# tiny.net
KiCad netlist of a schematic drawn in EAGLE
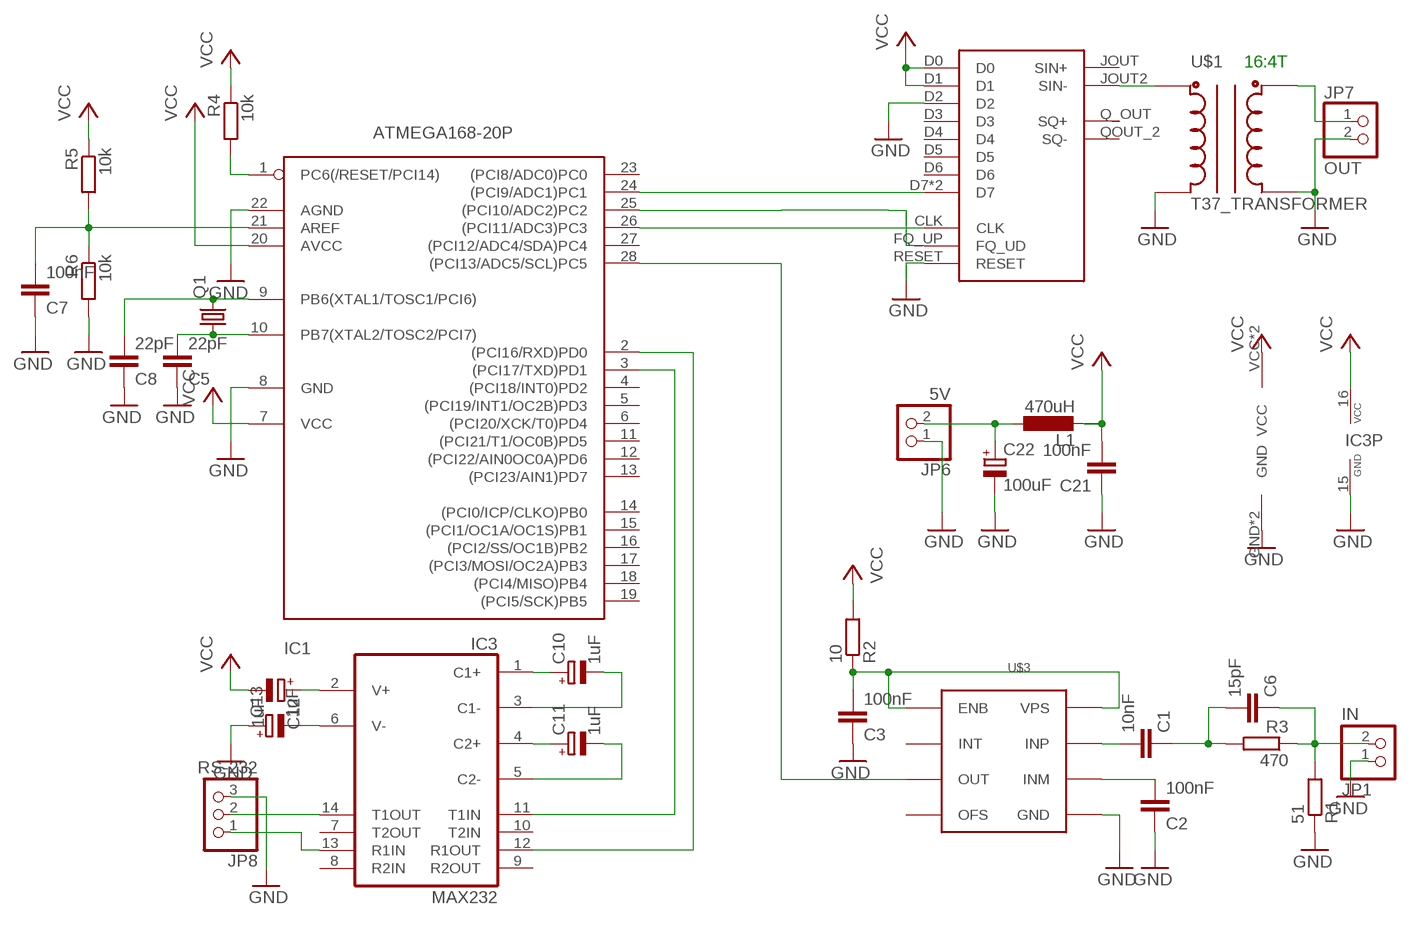
[diagram p0: schematic, sheet 1]

(export (version "E")
  (design (tool "Eeschema 10.0.6"))
  (components
    (comp (ref "C1")
      (value "10nF")
      (footprint "eagle-import:C050-025X075")
      (libsource (lib "eagle-import") (part "C-EU050-025X075"))
    )
    (comp (ref "C2")
      (value "100nF")
      (footprint "eagle-import:C025-025X050")
      (libsource (lib "eagle-import") (part "C-EU025-025X050"))
    )
    (comp (ref "C3")
      (value "100nF")
      (footprint "eagle-import:C025-025X050")
      (libsource (lib "eagle-import") (part "C-EU025-025X050"))
    )
    (comp (ref "C5")
      (value "22pF")
      (footprint "eagle-import:C050-025X075")
      (libsource (lib "eagle-import") (part "C-EU050-025X075"))
    )
    (comp (ref "C6")
      (value "15pF")
      (footprint "eagle-import:C050-025X075")
      (libsource (lib "eagle-import") (part "C-EU050-025X075"))
    )
    (comp (ref "C7")
      (value "100nF")
      (footprint "eagle-import:C025-025X050")
      (libsource (lib "eagle-import") (part "C-EU025-025X050"))
    )
    (comp (ref "C8")
      (value "22pF")
      (footprint "eagle-import:C025-025X050")
      (libsource (lib "eagle-import") (part "C-EU025-025X050"))
    )
    (comp (ref "C10")
      (value "1uF")
      (footprint "eagle-import:E5-5")
      (libsource (lib "eagle-import") (part "CPOL-EUE5-5"))
    )
    (comp (ref "C11")
      (value "1uF")
      (footprint "eagle-import:E2,5-5")
      (libsource (lib "eagle-import") (part "CPOL-EUE2.5-5"))
    )
    (comp (ref "C12")
      (value "1uF")
      (footprint "eagle-import:E2,5-6")
      (libsource (lib "eagle-import") (part "CPOL-EUE2.5-6"))
    )
    (comp (ref "C13")
      (value "1uF")
      (footprint "eagle-import:E5-5")
      (libsource (lib "eagle-import") (part "CPOL-EUE5-5"))
    )
    (comp (ref "C21")
      (value "100nF")
      (footprint "eagle-import:C025-025X050")
      (libsource (lib "eagle-import") (part "C-EU025-025X050"))
    )
    (comp (ref "C22")
      (value "100uF")
      (footprint "eagle-import:E2,5-6")
      (libsource (lib "eagle-import") (part "CPOL-EUE2.5-6"))
    )
    (comp (ref "IC1")
      (value "ATMEGA168-20P")
      (footprint "eagle-import:DIL28-3")
      (libsource (lib "eagle-import") (part "ATMEGA168P-20"))
    )
    (comp (ref "IC3")
      (value "MAX232")
      (footprint "eagle-import:DIL16")
      (fields (field (name "MF") "MAXIM") (field (name "MPN") "MAX232ACPE+"))
      (libsource (lib "eagle-import") (part "MAX232"))
    )
    (comp (ref "JP1")
      (value "IN")
      (footprint "eagle-import:1X02")
      (libsource (lib "eagle-import") (part "PINHD-1X2"))
    )
    (comp (ref "JP6")
      (value "5V")
      (footprint "eagle-import:1X02")
      (libsource (lib "eagle-import") (part "PINHD-1X2"))
    )
    (comp (ref "JP7")
      (value "OUT")
      (footprint "eagle-import:1X02")
      (libsource (lib "eagle-import") (part "PINHD-1X2"))
    )
    (comp (ref "JP8")
      (value "RS-232")
      (footprint "eagle-import:1X03")
      (libsource (lib "eagle-import") (part "PINHD-1X3"))
    )
    (comp (ref "L1")
      (value "470uH")
      (footprint "eagle-import:0204_7")
      (libsource (lib "eagle-import") (part "L-EU0204/7"))
    )
    (comp (ref "Q1")
      (value "CRYSTALHC18U-V")
      (footprint "eagle-import:HC18U-V")
      (libsource (lib "eagle-import") (part "CRYSTALHC18U-V"))
    )
    (comp (ref "R1")
      (value "51")
      (footprint "eagle-import:0204V")
      (libsource (lib "eagle-import") (part "R-EU_0204/2V"))
    )
    (comp (ref "R2")
      (value "10")
      (footprint "eagle-import:0204_7")
      (libsource (lib "eagle-import") (part "R-EU_0204/7"))
    )
    (comp (ref "R3")
      (value "470")
      (footprint "eagle-import:0204_5")
      (libsource (lib "eagle-import") (part "R-EU_0204/5"))
    )
    (comp (ref "R4")
      (value "10k")
      (footprint "eagle-import:0204_7")
      (libsource (lib "eagle-import") (part "R-EU_0204/7"))
    )
    (comp (ref "R5")
      (value "10k")
      (footprint "eagle-import:0204V")
      (libsource (lib "eagle-import") (part "R-EU_0204/2V"))
    )
    (comp (ref "R6")
      (value "10k")
      (footprint "eagle-import:0204V")
      (libsource (lib "eagle-import") (part "R-EU_0204/2V"))
    )
    (comp (ref "U$1")
      (value "T37_TRANSFORMER")
      (footprint "eagle-import:T37_TRANSFORMER")
      (libsource (lib "eagle-import") (part "T37_TRANSFORMER"))
    )
    (comp (ref "U$2")
      (value "DDS-1")
      (footprint "eagle-import:DDS-1")
      (libsource (lib "eagle-import") (part "DDS-1"))
    )
    (comp (ref "U$3")
      (value "AD8307")
      (footprint "eagle-import:DIL08")
      (libsource (lib "eagle-import") (part "AD8307"))
    )
  )
  (nets
    (net (code "1") (name "GND") (class "Default")
      (node (ref "C13") (pin "+") (pinfunction "+_+") (pintype "passive"))
      (node (ref "C2") (pin "1") (pinfunction "1_1") (pintype "passive"))
      (node (ref "C21") (pin "1") (pinfunction "1_1") (pintype "passive"))
      (node (ref "C22") (pin "-") (pinfunction "-_-") (pintype "passive"))
      (node (ref "C3") (pin "1") (pinfunction "1_1") (pintype "passive"))
      (node (ref "C5") (pin "1") (pinfunction "1_1") (pintype "passive"))
      (node (ref "C7") (pin "1") (pinfunction "1_1") (pintype "passive"))
      (node (ref "C8") (pin "1") (pinfunction "1_1") (pintype "passive"))
      (node (ref "IC1") (pin "22") (pinfunction "AGND_22") (pintype "bidirectional"))
      (node (ref "IC1") (pin "8") (pinfunction "GND_8") (pintype "bidirectional"))
      (node (ref "IC3") (pin "15") (pinfunction "GND_15") (pintype "power_in"))
      (node (ref "JP1") (pin "1") (pinfunction "1_1") (pintype "passive"))
      (node (ref "JP6") (pin "1") (pinfunction "1_1") (pintype "passive"))
      (node (ref "JP7") (pin "2") (pinfunction "2_2") (pintype "passive"))
      (node (ref "JP8") (pin "3") (pinfunction "3_3") (pintype "passive"))
      (node (ref "R1") (pin "1") (pinfunction "1_1") (pintype "passive"))
      (node (ref "R6") (pin "2") (pinfunction "2_2") (pintype "passive"))
      (node (ref "U$1") (pin "C1A") (pinfunction "C1A_C1A") (pintype "bidirectional"))
      (node (ref "U$1") (pin "C2A") (pinfunction "C2A_C2A") (pintype "bidirectional"))
      (node (ref "U$2") (pin "D2") (pinfunction "D2_D2") (pintype "bidirectional"))
      (node (ref "U$2") (pin "GND") (pinfunction "GND_GND") (pintype "bidirectional"))
      (node (ref "U$2") (pin "GND2") (pinfunction "GND_GND2") (pintype "bidirectional"))
      (node (ref "U$2") (pin "RESET") (pinfunction "RESET_RESET") (pintype "bidirectional"))
      (node (ref "U$3") (pin "2") (pinfunction "GND_2") (pintype "bidirectional"))
    )
    (net (code "2") (name "Net-(C1-Pad1)") (class "Default")
      (node (ref "C1") (pin "1") (pinfunction "1_1") (pintype "passive"))
      (node (ref "C6") (pin "2") (pinfunction "2_2") (pintype "passive"))
      (node (ref "R3") (pin "2") (pinfunction "2_2") (pintype "passive"))
    )
    (net (code "3") (name "Net-(C6-Pad1)") (class "Default")
      (node (ref "C6") (pin "1") (pinfunction "1_1") (pintype "passive"))
      (node (ref "JP1") (pin "2") (pinfunction "2_2") (pintype "passive"))
      (node (ref "R1") (pin "2") (pinfunction "2_2") (pintype "passive"))
      (node (ref "R3") (pin "1") (pinfunction "1_1") (pintype "passive"))
    )
    (net (code "4") (name "Net-(C22-Pad+)") (class "Default")
      (node (ref "C22") (pin "+") (pinfunction "+_+") (pintype "passive"))
      (node (ref "JP6") (pin "2") (pinfunction "2_2") (pintype "passive"))
      (node (ref "L1") (pin "1") (pinfunction "1_1") (pintype "passive"))
    )
    (net (code "5") (name "Net-(IC1-(PCI9{slash}ADC1)PC1)") (class "Default")
      (node (ref "IC1") (pin "24") (pinfunction "(PCI9/ADC1)PC1_24") (pintype "bidirectional"))
      (node (ref "U$2") (pin "D7") (pinfunction "D7_D7") (pintype "bidirectional"))
      (node (ref "U$2") (pin "D7_2") (pinfunction "D7_D7_2") (pintype "bidirectional"))
    )
    (net (code "6") (name "Net-(IC1-(PCI10{slash}ADC2)PC2)") (class "Default")
      (node (ref "IC1") (pin "25") (pinfunction "(PCI10/ADC2)PC2_25") (pintype "bidirectional"))
      (node (ref "U$2") (pin "FQ_UP") (pinfunction "FQ_UD_FQ_UP") (pintype "bidirectional"))
    )
    (net (code "7") (name "Net-(IC1-(PCI11{slash}ADC3)PC3)") (class "Default")
      (node (ref "IC1") (pin "26") (pinfunction "(PCI11/ADC3)PC3_26") (pintype "bidirectional"))
      (node (ref "U$2") (pin "CLK") (pinfunction "CLK_CLK") (pintype "bidirectional"))
    )
    (net (code "8") (name "Net-(IC1-(PCI13{slash}ADC5{slash}SCL)PC5)") (class "Default")
      (node (ref "IC1") (pin "28") (pinfunction "(PCI13/ADC5/SCL)PC5_28") (pintype "bidirectional"))
      (node (ref "U$3") (pin "4") (pinfunction "OUT_4") (pintype "bidirectional"))
    )
    (net (code "9") (name "Net-(IC1-(PCI16{slash}RXD)PD0)") (class "Default")
      (node (ref "IC1") (pin "2") (pinfunction "(PCI16/RXD)PD0_2") (pintype "bidirectional"))
      (node (ref "IC3") (pin "12") (pinfunction "R1OUT_12") (pintype "output"))
    )
    (net (code "10") (name "Net-(IC1-(PCI17{slash}TXD)PD1)") (class "Default")
      (node (ref "IC1") (pin "3") (pinfunction "(PCI17/TXD)PD1_3") (pintype "bidirectional"))
      (node (ref "IC3") (pin "11") (pinfunction "T1IN_11") (pintype "input"))
    )
    (net (code "11") (name "Net-(IC1-AREF)") (class "Default")
      (node (ref "C7") (pin "2") (pinfunction "2_2") (pintype "passive"))
      (node (ref "IC1") (pin "21") (pinfunction "AREF_21") (pintype "bidirectional"))
      (node (ref "R5") (pin "2") (pinfunction "2_2") (pintype "passive"))
      (node (ref "R6") (pin "1") (pinfunction "1_1") (pintype "passive"))
    )
    (net (code "12") (name "Net-(IC1-PB6(XTAL1{slash}TOSC1{slash}PCI6))") (class "Default")
      (node (ref "C8") (pin "2") (pinfunction "2_2") (pintype "passive"))
      (node (ref "IC1") (pin "9") (pinfunction "PB6(XTAL1/TOSC1/PCI6)_9") (pintype "bidirectional"))
      (node (ref "Q1") (pin "2") (pinfunction "2_2") (pintype "passive"))
    )
    (net (code "13") (name "Net-(IC1-PB7(XTAL2{slash}TOSC2{slash}PCI7))") (class "Default")
      (node (ref "C5") (pin "2") (pinfunction "2_2") (pintype "passive"))
      (node (ref "IC1") (pin "10") (pinfunction "PB7(XTAL2/TOSC2/PCI7)_10") (pintype "bidirectional"))
      (node (ref "Q1") (pin "1") (pinfunction "1_1") (pintype "passive"))
    )
    (net (code "14") (name "Net-(IC1-PC6({slash}RESET{slash}PCI14))") (class "Default")
      (node (ref "IC1") (pin "1") (pinfunction "PC6(/RESET/PCI14)_1") (pintype "bidirectional"))
      (node (ref "R4") (pin "2") (pinfunction "2_2") (pintype "passive"))
    )
    (net (code "15") (name "Net-(IC3A-C1+)") (class "Default")
      (node (ref "C10") (pin "+") (pinfunction "+_+") (pintype "passive"))
      (node (ref "IC3") (pin "1") (pinfunction "C1+_1") (pintype "bidirectional"))
    )
    (net (code "16") (name "Net-(IC3A-C1-)") (class "Default")
      (node (ref "C10") (pin "-") (pinfunction "-_-") (pintype "passive"))
      (node (ref "IC3") (pin "3") (pinfunction "C1-_3") (pintype "bidirectional"))
    )
    (net (code "17") (name "Net-(IC3A-C2+)") (class "Default")
      (node (ref "C11") (pin "+") (pinfunction "+_+") (pintype "passive"))
      (node (ref "IC3") (pin "4") (pinfunction "C2+_4") (pintype "bidirectional"))
    )
    (net (code "18") (name "Net-(IC3A-C2-)") (class "Default")
      (node (ref "C11") (pin "-") (pinfunction "-_-") (pintype "passive"))
      (node (ref "IC3") (pin "5") (pinfunction "C2-_5") (pintype "bidirectional"))
    )
    (net (code "19") (name "Net-(IC3A-R1IN)") (class "Default")
      (node (ref "IC3") (pin "13") (pinfunction "R1IN_13") (pintype "input"))
      (node (ref "JP8") (pin "1") (pinfunction "1_1") (pintype "passive"))
    )
    (net (code "20") (name "Net-(IC3A-T1OUT)") (class "Default")
      (node (ref "IC3") (pin "14") (pinfunction "T1OUT_14") (pintype "output"))
      (node (ref "JP8") (pin "2") (pinfunction "2_2") (pintype "passive"))
    )
    (net (code "21") (name "Net-(IC3A-V+)") (class "Default")
      (node (ref "C12") (pin "+") (pinfunction "+_+") (pintype "passive"))
      (node (ref "IC3") (pin "2") (pinfunction "V+_2") (pintype "bidirectional"))
    )
    (net (code "22") (name "Net-(IC3A-V-)") (class "Default")
      (node (ref "C13") (pin "-") (pinfunction "-_-") (pintype "passive"))
      (node (ref "IC3") (pin "6") (pinfunction "V-_6") (pintype "bidirectional"))
    )
    (net (code "23") (name "Net-(JP7-Pad1)") (class "Default")
      (node (ref "JP7") (pin "1") (pinfunction "1_1") (pintype "passive"))
      (node (ref "U$1") (pin "C2B") (pinfunction "C2B_C2B") (pintype "bidirectional"))
    )
    (net (code "24") (name "Net-(U$2A-SIN-)") (class "Default")
      (node (ref "U$1") (pin "C1B") (pinfunction "C1B_C1B") (pintype "bidirectional"))
      (node (ref "U$2") (pin "JOUT2") (pinfunction "SIN-_JOUT2") (pintype "bidirectional"))
    )
    (net (code "25") (name "Net-(U$3-ENB)") (class "Default")
      (node (ref "C3") (pin "2") (pinfunction "2_2") (pintype "passive"))
      (node (ref "R2") (pin "1") (pinfunction "1_1") (pintype "passive"))
      (node (ref "U$3") (pin "6") (pinfunction "ENB_6") (pintype "bidirectional"))
      (node (ref "U$3") (pin "7") (pinfunction "VPS_7") (pintype "bidirectional"))
    )
    (net (code "26") (name "Net-(U$3-INM)") (class "Default")
      (node (ref "C2") (pin "2") (pinfunction "2_2") (pintype "passive"))
      (node (ref "U$3") (pin "1") (pinfunction "INM_1") (pintype "bidirectional"))
    )
    (net (code "27") (name "Net-(U$3-INP)") (class "Default")
      (node (ref "C1") (pin "2") (pinfunction "2_2") (pintype "passive"))
      (node (ref "U$3") (pin "8") (pinfunction "INP_8") (pintype "bidirectional"))
    )
    (net (code "28") (name "VCC") (class "Default")
      (node (ref "C12") (pin "-") (pinfunction "-_-") (pintype "passive"))
      (node (ref "C21") (pin "2") (pinfunction "2_2") (pintype "passive"))
      (node (ref "IC1") (pin "20") (pinfunction "AVCC_20") (pintype "bidirectional"))
      (node (ref "IC1") (pin "7") (pinfunction "VCC_7") (pintype "bidirectional"))
      (node (ref "IC3") (pin "16") (pinfunction "VCC_16") (pintype "power_in"))
      (node (ref "L1") (pin "2") (pinfunction "2_2") (pintype "passive"))
      (node (ref "R2") (pin "2") (pinfunction "2_2") (pintype "passive"))
      (node (ref "R4") (pin "1") (pinfunction "1_1") (pintype "passive"))
      (node (ref "R5") (pin "1") (pinfunction "1_1") (pintype "passive"))
      (node (ref "U$2") (pin "D0") (pinfunction "D0_D0") (pintype "bidirectional"))
      (node (ref "U$2") (pin "D1") (pinfunction "D1_D1") (pintype "bidirectional"))
      (node (ref "U$2") (pin "VCC") (pinfunction "VCC_VCC") (pintype "bidirectional"))
      (node (ref "U$2") (pin "VCC2") (pinfunction "VCC_VCC2") (pintype "bidirectional"))
    )
    (net (code "29") (name "unconnected-(IC1-(PCI0{slash}ICP{slash}CLKO)PB0-Pad14)") (class "Default")
      (node (ref "IC1") (pin "14") (pinfunction "(PCI0/ICP/CLKO)PB0_14") (pintype "bidirectional"))
    )
    (net (code "30") (name "unconnected-(IC1-(PCI1{slash}OC1A{slash}OC1S)PB1-Pad15)") (class "Default")
      (node (ref "IC1") (pin "15") (pinfunction "(PCI1/OC1A/OC1S)PB1_15") (pintype "bidirectional"))
    )
    (net (code "31") (name "unconnected-(IC1-(PCI2{slash}SS{slash}OC1B)PB2-Pad16)") (class "Default")
      (node (ref "IC1") (pin "16") (pinfunction "(PCI2/SS/OC1B)PB2_16") (pintype "bidirectional"))
    )
    (net (code "32") (name "unconnected-(IC1-(PCI3{slash}MOSI{slash}OC2A)PB3-Pad17)") (class "Default")
      (node (ref "IC1") (pin "17") (pinfunction "(PCI3/MOSI/OC2A)PB3_17") (pintype "bidirectional"))
    )
    (net (code "33") (name "unconnected-(IC1-(PCI4{slash}MISO)PB4-Pad18)") (class "Default")
      (node (ref "IC1") (pin "18") (pinfunction "(PCI4/MISO)PB4_18") (pintype "bidirectional"))
    )
    (net (code "34") (name "unconnected-(IC1-(PCI5{slash}SCK)PB5-Pad19)") (class "Default")
      (node (ref "IC1") (pin "19") (pinfunction "(PCI5/SCK)PB5_19") (pintype "bidirectional"))
    )
    (net (code "35") (name "unconnected-(IC1-(PCI8{slash}ADC0)PC0-Pad23)") (class "Default")
      (node (ref "IC1") (pin "23") (pinfunction "(PCI8/ADC0)PC0_23") (pintype "bidirectional"))
    )
    (net (code "36") (name "unconnected-(IC1-(PCI12{slash}ADC4{slash}SDA)PC4-Pad27)") (class "Default")
      (node (ref "IC1") (pin "27") (pinfunction "(PCI12/ADC4/SDA)PC4_27") (pintype "bidirectional"))
    )
    (net (code "37") (name "unconnected-(IC1-(PCI18{slash}INT0)PD2-Pad4)") (class "Default")
      (node (ref "IC1") (pin "4") (pinfunction "(PCI18/INT0)PD2_4") (pintype "bidirectional"))
    )
    (net (code "38") (name "unconnected-(IC1-(PCI19{slash}INT1{slash}OC2B)PD3-Pad5)") (class "Default")
      (node (ref "IC1") (pin "5") (pinfunction "(PCI19/INT1/OC2B)PD3_5") (pintype "bidirectional"))
    )
    (net (code "39") (name "unconnected-(IC1-(PCI20{slash}XCK{slash}T0)PD4-Pad6)") (class "Default")
      (node (ref "IC1") (pin "6") (pinfunction "(PCI20/XCK/T0)PD4_6") (pintype "bidirectional"))
    )
    (net (code "40") (name "unconnected-(IC1-(PCI21{slash}T1{slash}OC0B)PD5-Pad11)") (class "Default")
      (node (ref "IC1") (pin "11") (pinfunction "(PCI21/T1/OC0B)PD5_11") (pintype "bidirectional"))
    )
    (net (code "41") (name "unconnected-(IC1-(PCI22{slash}AIN0OC0A)PD6-Pad12)") (class "Default")
      (node (ref "IC1") (pin "12") (pinfunction "(PCI22/AIN0OC0A)PD6_12") (pintype "bidirectional"))
    )
    (net (code "42") (name "unconnected-(IC1-(PCI23{slash}AIN1)PD7-Pad13)") (class "Default")
      (node (ref "IC1") (pin "13") (pinfunction "(PCI23/AIN1)PD7_13") (pintype "bidirectional"))
    )
    (net (code "43") (name "unconnected-(IC3A-R2IN-Pad8)") (class "Default")
      (node (ref "IC3") (pin "8") (pinfunction "R2IN_8") (pintype "input"))
    )
    (net (code "44") (name "unconnected-(IC3A-R2OUT-Pad9)") (class "Default")
      (node (ref "IC3") (pin "9") (pinfunction "R2OUT_9") (pintype "output"))
    )
    (net (code "45") (name "unconnected-(IC3A-T2IN-Pad10)") (class "Default")
      (node (ref "IC3") (pin "10") (pinfunction "T2IN_10") (pintype "input"))
    )
    (net (code "46") (name "unconnected-(IC3A-T2OUT-Pad7)") (class "Default")
      (node (ref "IC3") (pin "7") (pinfunction "T2OUT_7") (pintype "output"))
    )
    (net (code "47") (name "unconnected-(U$2-PadD3)") (class "Default")
      (node (ref "U$2") (pin "D3") (pinfunction "D3_D3") (pintype "bidirectional"))
    )
    (net (code "48") (name "unconnected-(U$2-PadD4)") (class "Default")
      (node (ref "U$2") (pin "D4") (pinfunction "D4_D4") (pintype "bidirectional"))
    )
    (net (code "49") (name "unconnected-(U$2-PadD5)") (class "Default")
      (node (ref "U$2") (pin "D5") (pinfunction "D5_D5") (pintype "bidirectional"))
    )
    (net (code "50") (name "unconnected-(U$2-PadD6)") (class "Default")
      (node (ref "U$2") (pin "D6") (pinfunction "D6_D6") (pintype "bidirectional"))
    )
    (net (code "51") (name "unconnected-(U$2A-SIN+-PadJOUT)") (class "Default")
      (node (ref "U$2") (pin "JOUT") (pinfunction "SIN+_JOUT") (pintype "bidirectional"))
    )
    (net (code "52") (name "unconnected-(U$2A-SQ+-PadQ_OUT)") (class "Default")
      (node (ref "U$2") (pin "Q_OUT") (pinfunction "SQ+_Q_OUT") (pintype "bidirectional"))
    )
    (net (code "53") (name "unconnected-(U$2A-SQ--PadQOUT_2)") (class "Default")
      (node (ref "U$2") (pin "QOUT_2") (pinfunction "SQ-_QOUT_2") (pintype "bidirectional"))
    )
    (net (code "54") (name "unconnected-(U$3-INT-Pad5)") (class "Default")
      (node (ref "U$3") (pin "5") (pinfunction "INT_5") (pintype "bidirectional"))
    )
    (net (code "55") (name "unconnected-(U$3-OFS-Pad3)") (class "Default")
      (node (ref "U$3") (pin "3") (pinfunction "OFS_3") (pintype "bidirectional"))
    )
  )
)
